# nrf52832_E73_breakout_rev_1.net
KiCad netlist of a schematic drawn in EAGLE
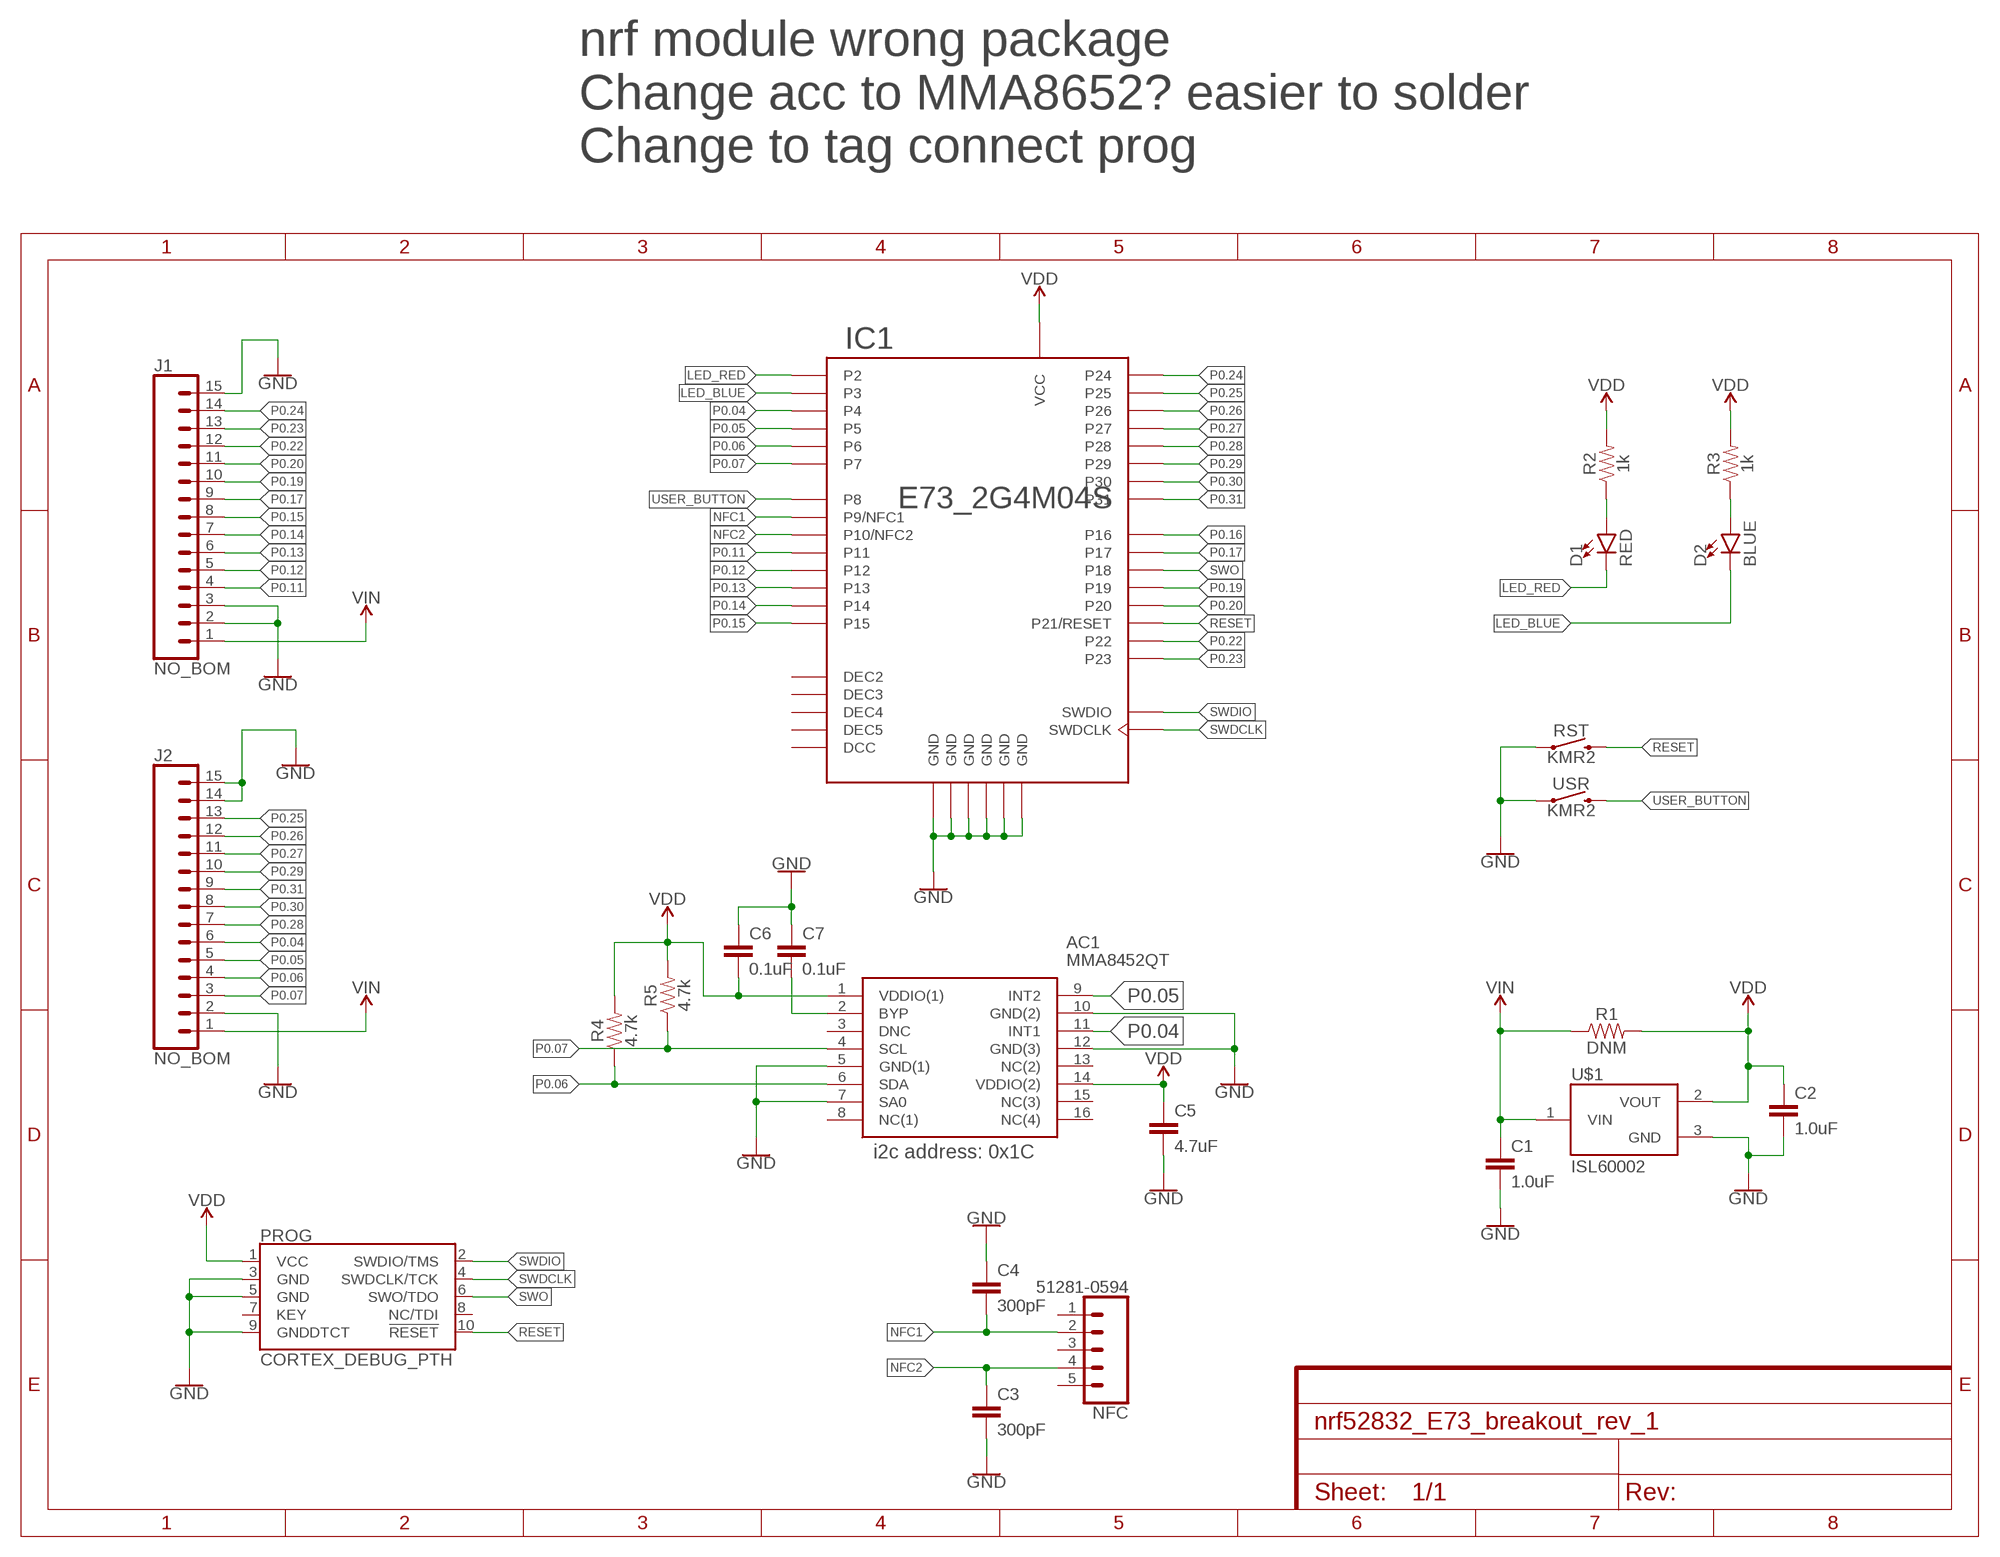
[diagram p0: schematic, sheet 1]

(export (version "E")
  (design (tool "Eeschema 10.0.6"))
  (components
    (comp (ref "AC1")
      (value "MMA8452QT")
      (footprint "eagle-import:PQFN50P300X300X100-16N")
      (fields (field (name "RS_PART_NUMBER") "9227526"))
      (libsource (lib "eagle-import") (part "MMA8452QT"))
    )
    (comp (ref "C1")
      (value "1.0uF")
      (footprint "eagle-import:C0603")
      (libsource (lib "eagle-import") (part "CAP-16V-20%-0603"))
    )
    (comp (ref "C2")
      (value "1.0uF")
      (footprint "eagle-import:C0603")
      (libsource (lib "eagle-import") (part "CAP-6.3V-20%-0603"))
    )
    (comp (ref "C3")
      (value "300pF")
      (footprint "eagle-import:C0402")
      (libsource (lib "eagle-import") (part "CAP-6.3V-20%-0402"))
    )
    (comp (ref "C4")
      (value "300pF")
      (footprint "eagle-import:C0402")
      (libsource (lib "eagle-import") (part "CAP-6.3V-20%-0402"))
    )
    (comp (ref "C5")
      (value "4.7uF")
      (footprint "eagle-import:C0603")
      (libsource (lib "eagle-import") (part "CAP-6.3V-20%-0603"))
    )
    (comp (ref "C6")
      (value "0.1uF")
      (footprint "eagle-import:C0402")
      (libsource (lib "eagle-import") (part "CAP-6.3V-20%-0402"))
    )
    (comp (ref "C7")
      (value "0.1uF")
      (footprint "eagle-import:C0402")
      (libsource (lib "eagle-import") (part "CAP-6.3V-20%-0402"))
    )
    (comp (ref "D1")
      (value "RED")
      (footprint "eagle-import:LED-0603")
      (libsource (lib "eagle-import") (part "LED0603"))
    )
    (comp (ref "D2")
      (value "BLUE")
      (footprint "eagle-import:LED-0603")
      (libsource (lib "eagle-import") (part "LED0603"))
    )
    (comp (ref "IC1")
      (value "E73_2G4M04S")
      (footprint "eagle-import:E73_2G4M04S")
      (libsource (lib "eagle-import") (part "E73_2G4M04S"))
    )
    (comp (ref "J1")
      (value "NO_BOM")
      (footprint "eagle-import:1X15")
      (libsource (lib "eagle-import") (part "CONN_15"))
    )
    (comp (ref "J2")
      (value "NO_BOM")
      (footprint "eagle-import:1X15")
      (libsource (lib "eagle-import") (part "CONN_15"))
    )
    (comp (ref "NFC")
      (value "51281-0594")
      (footprint "eagle-import:51281-0594")
      (libsource (lib "eagle-import") (part "51281-0594"))
    )
    (comp (ref "PROG")
      (value "CORTEX_DEBUG_PTH")
      (footprint "eagle-import:2X5-PTH-1.27MM")
      (libsource (lib "eagle-import") (part "CORTEX_DEBUG_PTH"))
    )
    (comp (ref "R1")
      (value "DNM")
      (footprint "eagle-import:R0603")
      (libsource (lib "eagle-import") (part "RES-0.063W-5%-0603"))
    )
    (comp (ref "R2")
      (value "1k")
      (footprint "eagle-import:R0603")
      (libsource (lib "eagle-import") (part "RES-0.063W-5%-0603"))
    )
    (comp (ref "R3")
      (value "1k")
      (footprint "eagle-import:R0603")
      (libsource (lib "eagle-import") (part "RES-0.063W-5%-0603"))
    )
    (comp (ref "R4")
      (value "4.7k")
      (footprint "eagle-import:R0402")
      (libsource (lib "eagle-import") (part "RES-0.063W-5%-0402"))
    )
    (comp (ref "R5")
      (value "4.7k")
      (footprint "eagle-import:R0402")
      (libsource (lib "eagle-import") (part "RES-0.063W-5%-0402"))
    )
    (comp (ref "RST")
      (value "KMR2")
      (footprint "eagle-import:TACTILE_SWITCH_SMD_4.6X2.8MM")
      (fields (field (name "MANUFACTURER_PART_NUMBER") "KMR211GLFS"))
      (libsource (lib "eagle-import") (part "KMR2"))
    )
    (comp (ref "U$1")
      (value "ISL60002")
      (footprint "eagle-import:SOT23-3")
      (libsource (lib "eagle-import") (part "ISL60002"))
    )
    (comp (ref "USR")
      (value "KMR2")
      (footprint "eagle-import:TACTILE_SWITCH_SMD_4.6X2.8MM")
      (fields (field (name "MANUFACTURER_PART_NUMBER") "KMR211GLFS"))
      (libsource (lib "eagle-import") (part "KMR2"))
    )
  )
  (nets
    (net (code "1") (name "/DCC") (class "Default")
      (node (ref "IC1") (pin "13") (pinfunction "DCC_13") (pintype "power_in"))
    )
    (net (code "2") (name "/DEC2") (class "Default")
      (node (ref "IC1") (pin "3") (pinfunction "DEC2_3") (pintype "power_in"))
    )
    (net (code "3") (name "/DEC3") (class "Default")
      (node (ref "IC1") (pin "4") (pinfunction "DEC3_4") (pintype "power_in"))
    )
    (net (code "4") (name "/DEC4") (class "Default")
      (node (ref "IC1") (pin "12") (pinfunction "DEC4_12") (pintype "power_in"))
    )
    (net (code "5") (name "/DEC5") (class "Default")
      (node (ref "IC1") (pin "14") (pinfunction "DEC5_14") (pintype "power_in"))
    )
    (net (code "6") (name "GND") (class "Default")
      (node (ref "AC1") (pin "10") (pinfunction "GND(2)_10") (pintype "input"))
      (node (ref "AC1") (pin "12") (pinfunction "GND(3)_12") (pintype "input"))
      (node (ref "AC1") (pin "5") (pinfunction "GND(1)_5") (pintype "input"))
      (node (ref "AC1") (pin "7") (pinfunction "SA0_7") (pintype "input"))
      (node (ref "C1") (pin "2") (pinfunction "2_2") (pintype "passive"))
      (node (ref "C2") (pin "2") (pinfunction "2_2") (pintype "passive"))
      (node (ref "C3") (pin "2") (pinfunction "2_2") (pintype "passive"))
      (node (ref "C4") (pin "1") (pinfunction "1_1") (pintype "passive"))
      (node (ref "C5") (pin "2") (pinfunction "2_2") (pintype "passive"))
      (node (ref "C6") (pin "1") (pinfunction "1_1") (pintype "passive"))
      (node (ref "C7") (pin "1") (pinfunction "1_1") (pintype "passive"))
      (node (ref "IC1") (pin "0") (pinfunction "GND_0") (pintype "bidirectional"))
      (node (ref "IC1") (pin "1") (pinfunction "GND_1") (pintype "bidirectional"))
      (node (ref "IC1") (pin "15") (pinfunction "GND_15") (pintype "bidirectional"))
      (node (ref "IC1") (pin "2") (pinfunction "GND_2") (pintype "bidirectional"))
      (node (ref "IC1") (pin "42") (pinfunction "GND_42") (pintype "bidirectional"))
      (node (ref "IC1") (pin "43") (pinfunction "GND_43") (pintype "bidirectional"))
      (node (ref "J1") (pin "15") (pinfunction "15_15") (pintype "passive"))
      (node (ref "J1") (pin "2") (pinfunction "2_2") (pintype "passive"))
      (node (ref "J1") (pin "3") (pinfunction "3_3") (pintype "passive"))
      (node (ref "J2") (pin "14") (pinfunction "14_14") (pintype "passive"))
      (node (ref "J2") (pin "15") (pinfunction "15_15") (pintype "passive"))
      (node (ref "J2") (pin "2") (pinfunction "2_2") (pintype "passive"))
      (node (ref "PROG") (pin "3") (pinfunction "GND_3") (pintype "bidirectional"))
      (node (ref "PROG") (pin "5") (pinfunction "GND_5") (pintype "bidirectional"))
      (node (ref "PROG") (pin "9") (pinfunction "GNDDTCT_9") (pintype "bidirectional"))
      (node (ref "RST") (pin "1") (pinfunction "1_1") (pintype "passive"))
      (node (ref "RST") (pin "2") (pinfunction "1_2") (pintype "passive"))
      (node (ref "U$1") (pin "3") (pinfunction "GND_3") (pintype "bidirectional"))
      (node (ref "USR") (pin "1") (pinfunction "1_1") (pintype "passive"))
      (node (ref "USR") (pin "2") (pinfunction "1_2") (pintype "passive"))
    )
    (net (code "7") (name "LED_BLUE") (class "Default")
      (node (ref "D2") (pin "C") (pinfunction "C_C") (pintype "passive"))
      (node (ref "IC1") (pin "18") (pinfunction "P3_18") (pintype "bidirectional"))
    )
    (net (code "8") (name "LED_RED") (class "Default")
      (node (ref "D1") (pin "C") (pinfunction "C_C") (pintype "passive"))
      (node (ref "IC1") (pin "17") (pinfunction "P2_17") (pintype "bidirectional"))
    )
    (net (code "9") (name "NFC1") (class "Default")
      (node (ref "C4") (pin "2") (pinfunction "2_2") (pintype "passive"))
      (node (ref "IC1") (pin "24") (pinfunction "P9/NFC1_24") (pintype "bidirectional"))
      (node (ref "NFC") (pin "2") (pinfunction "2_2") (pintype "passive"))
    )
    (net (code "10") (name "NFC2") (class "Default")
      (node (ref "C3") (pin "1") (pinfunction "1_1") (pintype "passive"))
      (node (ref "IC1") (pin "25") (pinfunction "P10/NFC2_25") (pintype "bidirectional"))
      (node (ref "NFC") (pin "4") (pinfunction "4_4") (pintype "passive"))
    )
    (net (code "11") (name "Net-(AC1-BYP)") (class "Default")
      (node (ref "AC1") (pin "2") (pinfunction "BYP_2") (pintype "input"))
      (node (ref "C7") (pin "2") (pinfunction "2_2") (pintype "passive"))
    )
    (net (code "12") (name "Net-(D1-PadA)") (class "Default")
      (node (ref "D1") (pin "A") (pinfunction "A_A") (pintype "passive"))
      (node (ref "R2") (pin "1") (pinfunction "1_1") (pintype "passive"))
    )
    (net (code "13") (name "Net-(D2-PadA)") (class "Default")
      (node (ref "D2") (pin "A") (pinfunction "A_A") (pintype "passive"))
      (node (ref "R3") (pin "1") (pinfunction "1_1") (pintype "passive"))
    )
    (net (code "14") (name "P0.04") (class "Default")
      (node (ref "AC1") (pin "11") (pinfunction "INT1_11") (pintype "input"))
      (node (ref "IC1") (pin "19") (pinfunction "P4_19") (pintype "bidirectional"))
      (node (ref "J2") (pin "6") (pinfunction "6_6") (pintype "passive"))
    )
    (net (code "15") (name "P0.05") (class "Default")
      (node (ref "AC1") (pin "9") (pinfunction "INT2_9") (pintype "input"))
      (node (ref "IC1") (pin "20") (pinfunction "P5_20") (pintype "bidirectional"))
      (node (ref "J2") (pin "5") (pinfunction "5_5") (pintype "passive"))
    )
    (net (code "16") (name "P0.06") (class "Default")
      (node (ref "AC1") (pin "6") (pinfunction "SDA_6") (pintype "input"))
      (node (ref "IC1") (pin "21") (pinfunction "P6_21") (pintype "bidirectional"))
      (node (ref "J2") (pin "4") (pinfunction "4_4") (pintype "passive"))
      (node (ref "R4") (pin "1") (pinfunction "1_1") (pintype "passive"))
    )
    (net (code "17") (name "P0.07") (class "Default")
      (node (ref "AC1") (pin "4") (pinfunction "SCL_4") (pintype "input"))
      (node (ref "IC1") (pin "22") (pinfunction "P7_22") (pintype "bidirectional"))
      (node (ref "J2") (pin "3") (pinfunction "3_3") (pintype "passive"))
      (node (ref "R5") (pin "1") (pinfunction "1_1") (pintype "passive"))
    )
    (net (code "18") (name "P0.11") (class "Default")
      (node (ref "IC1") (pin "26") (pinfunction "P11_26") (pintype "bidirectional"))
      (node (ref "J1") (pin "4") (pinfunction "4_4") (pintype "passive"))
    )
    (net (code "19") (name "P0.12") (class "Default")
      (node (ref "IC1") (pin "27") (pinfunction "P12_27") (pintype "bidirectional"))
      (node (ref "J1") (pin "5") (pinfunction "5_5") (pintype "passive"))
    )
    (net (code "20") (name "P0.13") (class "Default")
      (node (ref "IC1") (pin "28") (pinfunction "P13_28") (pintype "bidirectional"))
      (node (ref "J1") (pin "6") (pinfunction "6_6") (pintype "passive"))
    )
    (net (code "21") (name "P0.14") (class "Default")
      (node (ref "IC1") (pin "29") (pinfunction "P14_29") (pintype "bidirectional"))
      (node (ref "J1") (pin "7") (pinfunction "7_7") (pintype "passive"))
    )
    (net (code "22") (name "P0.15") (class "Default")
      (node (ref "IC1") (pin "30") (pinfunction "P15_30") (pintype "bidirectional"))
      (node (ref "J1") (pin "8") (pinfunction "8_8") (pintype "passive"))
    )
    (net (code "23") (name "P0.16") (class "Default")
      (node (ref "IC1") (pin "31") (pinfunction "P16_31") (pintype "bidirectional"))
    )
    (net (code "24") (name "P0.17") (class "Default")
      (node (ref "IC1") (pin "32") (pinfunction "P17_32") (pintype "bidirectional"))
      (node (ref "J1") (pin "9") (pinfunction "9_9") (pintype "passive"))
    )
    (net (code "25") (name "P0.19") (class "Default")
      (node (ref "IC1") (pin "34") (pinfunction "P19_34") (pintype "bidirectional"))
      (node (ref "J1") (pin "10") (pinfunction "10_10") (pintype "passive"))
    )
    (net (code "26") (name "P0.20") (class "Default")
      (node (ref "IC1") (pin "35") (pinfunction "P20_35") (pintype "bidirectional"))
      (node (ref "J1") (pin "11") (pinfunction "11_11") (pintype "passive"))
    )
    (net (code "27") (name "P0.22") (class "Default")
      (node (ref "IC1") (pin "39") (pinfunction "P22_39") (pintype "bidirectional"))
      (node (ref "J1") (pin "12") (pinfunction "12_12") (pintype "passive"))
    )
    (net (code "28") (name "P0.23") (class "Default")
      (node (ref "IC1") (pin "40") (pinfunction "P23_40") (pintype "bidirectional"))
      (node (ref "J1") (pin "13") (pinfunction "13_13") (pintype "passive"))
    )
    (net (code "29") (name "P0.24") (class "Default")
      (node (ref "IC1") (pin "41") (pinfunction "P24_41") (pintype "bidirectional"))
      (node (ref "J1") (pin "14") (pinfunction "14_14") (pintype "passive"))
    )
    (net (code "30") (name "P0.25") (class "Default")
      (node (ref "IC1") (pin "5") (pinfunction "P25_5") (pintype "bidirectional"))
      (node (ref "J2") (pin "13") (pinfunction "13_13") (pintype "passive"))
    )
    (net (code "31") (name "P0.26") (class "Default")
      (node (ref "IC1") (pin "6") (pinfunction "P26_6") (pintype "bidirectional"))
      (node (ref "J2") (pin "12") (pinfunction "12_12") (pintype "passive"))
    )
    (net (code "32") (name "P0.27") (class "Default")
      (node (ref "IC1") (pin "7") (pinfunction "P27_7") (pintype "bidirectional"))
      (node (ref "J2") (pin "11") (pinfunction "11_11") (pintype "passive"))
    )
    (net (code "33") (name "P0.28") (class "Default")
      (node (ref "IC1") (pin "8") (pinfunction "P28_8") (pintype "bidirectional"))
      (node (ref "J2") (pin "7") (pinfunction "7_7") (pintype "passive"))
    )
    (net (code "34") (name "P0.29") (class "Default")
      (node (ref "IC1") (pin "9") (pinfunction "P29_9") (pintype "bidirectional"))
      (node (ref "J2") (pin "10") (pinfunction "10_10") (pintype "passive"))
    )
    (net (code "35") (name "P0.30") (class "Default")
      (node (ref "IC1") (pin "10") (pinfunction "P30_10") (pintype "bidirectional"))
      (node (ref "J2") (pin "8") (pinfunction "8_8") (pintype "passive"))
    )
    (net (code "36") (name "P0.31") (class "Default")
      (node (ref "IC1") (pin "11") (pinfunction "P31_11") (pintype "bidirectional"))
      (node (ref "J2") (pin "9") (pinfunction "9_9") (pintype "passive"))
    )
    (net (code "37") (name "RESET") (class "Default")
      (node (ref "IC1") (pin "36") (pinfunction "P21/RESET_36") (pintype "bidirectional"))
      (node (ref "PROG") (pin "10") (pinfunction "~{RESET}_10") (pintype "bidirectional"))
      (node (ref "RST") (pin "3") (pinfunction "2_3") (pintype "passive"))
      (node (ref "RST") (pin "4") (pinfunction "2_4") (pintype "passive"))
    )
    (net (code "38") (name "SWDCLK") (class "Default")
      (node (ref "IC1") (pin "37") (pinfunction "SWDCLK_37") (pintype "input"))
      (node (ref "PROG") (pin "4") (pinfunction "SWDCLK/TCK_4") (pintype "bidirectional"))
    )
    (net (code "39") (name "SWDIO") (class "Default")
      (node (ref "IC1") (pin "38") (pinfunction "SWDIO_38") (pintype "bidirectional"))
      (node (ref "PROG") (pin "2") (pinfunction "SWDIO/TMS_2") (pintype "bidirectional"))
    )
    (net (code "40") (name "SWO") (class "Default")
      (node (ref "IC1") (pin "33") (pinfunction "P18_33") (pintype "bidirectional"))
      (node (ref "PROG") (pin "6") (pinfunction "SWO/TDO_6") (pintype "bidirectional"))
    )
    (net (code "41") (name "USER_BUTTON") (class "Default")
      (node (ref "IC1") (pin "23") (pinfunction "P8_23") (pintype "bidirectional"))
      (node (ref "USR") (pin "3") (pinfunction "2_3") (pintype "passive"))
      (node (ref "USR") (pin "4") (pinfunction "2_4") (pintype "passive"))
    )
    (net (code "42") (name "VDD") (class "Default")
      (node (ref "AC1") (pin "1") (pinfunction "VDDIO(1)_1") (pintype "input"))
      (node (ref "AC1") (pin "14") (pinfunction "VDDIO(2)_14") (pintype "input"))
      (node (ref "C2") (pin "1") (pinfunction "1_1") (pintype "passive"))
      (node (ref "C5") (pin "1") (pinfunction "1_1") (pintype "passive"))
      (node (ref "C6") (pin "2") (pinfunction "2_2") (pintype "passive"))
      (node (ref "IC1") (pin "16") (pinfunction "VCC_16") (pintype "passive"))
      (node (ref "PROG") (pin "1") (pinfunction "VCC_1") (pintype "bidirectional"))
      (node (ref "R1") (pin "2") (pinfunction "2_2") (pintype "passive"))
      (node (ref "R2") (pin "2") (pinfunction "2_2") (pintype "passive"))
      (node (ref "R3") (pin "2") (pinfunction "2_2") (pintype "passive"))
      (node (ref "R4") (pin "2") (pinfunction "2_2") (pintype "passive"))
      (node (ref "R5") (pin "2") (pinfunction "2_2") (pintype "passive"))
      (node (ref "U$1") (pin "2") (pinfunction "VOUT_2") (pintype "bidirectional"))
    )
    (net (code "43") (name "VIN") (class "Default")
      (node (ref "C1") (pin "1") (pinfunction "1_1") (pintype "passive"))
      (node (ref "J1") (pin "1") (pinfunction "1_1") (pintype "passive"))
      (node (ref "J2") (pin "1") (pinfunction "1_1") (pintype "passive"))
      (node (ref "R1") (pin "1") (pinfunction "1_1") (pintype "passive"))
      (node (ref "U$1") (pin "1") (pinfunction "VIN_1") (pintype "bidirectional"))
    )
    (net (code "44") (name "unconnected-(AC1-DNC-Pad3)") (class "Default")
      (node (ref "AC1") (pin "3") (pinfunction "DNC_3") (pintype "input"))
    )
    (net (code "45") (name "unconnected-(AC1-NC(1)-Pad8)") (class "Default")
      (node (ref "AC1") (pin "8") (pinfunction "NC(1)_8") (pintype "input"))
    )
    (net (code "46") (name "unconnected-(AC1-NC(2)-Pad13)") (class "Default")
      (node (ref "AC1") (pin "13") (pinfunction "NC(2)_13") (pintype "input"))
    )
    (net (code "47") (name "unconnected-(AC1-NC(3)-Pad15)") (class "Default")
      (node (ref "AC1") (pin "15") (pinfunction "NC(3)_15") (pintype "input"))
    )
    (net (code "48") (name "unconnected-(AC1-NC(4)-Pad16)") (class "Default")
      (node (ref "AC1") (pin "16") (pinfunction "NC(4)_16") (pintype "input"))
    )
    (net (code "49") (name "unconnected-(NFC-Pad1)") (class "Default")
      (node (ref "NFC") (pin "1") (pinfunction "1_1") (pintype "passive"))
    )
    (net (code "50") (name "unconnected-(NFC-Pad3)") (class "Default")
      (node (ref "NFC") (pin "3") (pinfunction "3_3") (pintype "passive"))
    )
    (net (code "51") (name "unconnected-(NFC-Pad5)") (class "Default")
      (node (ref "NFC") (pin "5") (pinfunction "5_5") (pintype "passive"))
    )
    (net (code "52") (name "unconnected-(PROG-KEY-Pad7)") (class "Default")
      (node (ref "PROG") (pin "7") (pinfunction "KEY_7") (pintype "bidirectional"))
    )
    (net (code "53") (name "unconnected-(PROG-NC{slash}TDI-Pad8)") (class "Default")
      (node (ref "PROG") (pin "8") (pinfunction "NC/TDI_8") (pintype "bidirectional"))
    )
  )
)
